# 12V_UPS1.net
KiCad netlist of a schematic drawn in EAGLE
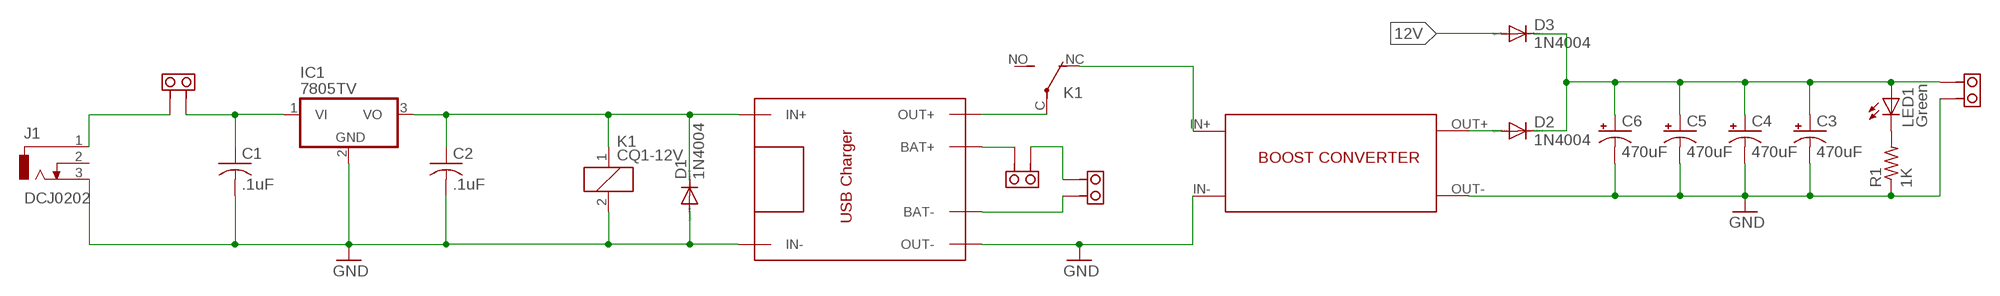
[diagram p0: schematic, sheet 1]

(export (version "E")
  (design (tool "Eeschema 10.0.6"))
  (components
    (comp (ref "C1")
      (value ".1uF")
      (footprint "eagle-import:C025-030X050")
      (libsource (lib "eagle-import") (part "C-US025-030X050"))
    )
    (comp (ref "C2")
      (value ".1uF")
      (footprint "eagle-import:C025-030X050")
      (libsource (lib "eagle-import") (part "C-US025-030X050"))
    )
    (comp (ref "C3")
      (value "470uF")
      (footprint "eagle-import:E5-8,5")
      (libsource (lib "eagle-import") (part "CPOL-USE5-8.5"))
    )
    (comp (ref "C4")
      (value "470uF")
      (footprint "eagle-import:E5-8,5")
      (libsource (lib "eagle-import") (part "CPOL-USE5-8.5"))
    )
    (comp (ref "C5")
      (value "470uF")
      (footprint "eagle-import:E5-8,5")
      (libsource (lib "eagle-import") (part "CPOL-USE5-8.5"))
    )
    (comp (ref "C6")
      (value "470uF")
      (footprint "eagle-import:E5-8,5")
      (libsource (lib "eagle-import") (part "CPOL-USE5-8.5"))
    )
    (comp (ref "D1")
      (value "1N4004")
      (footprint "eagle-import:DO41-10")
      (libsource (lib "eagle-import") (part "1N4004"))
    )
    (comp (ref "D2")
      (value "1N4004")
      (footprint "eagle-import:DO41-10")
      (libsource (lib "eagle-import") (part "1N4004"))
    )
    (comp (ref "D3")
      (value "1N4004")
      (footprint "eagle-import:DO41-10")
      (libsource (lib "eagle-import") (part "1N4004"))
    )
    (comp (ref "IC1")
      (value "7805TV")
      (footprint "eagle-import:TO220V")
      (libsource (lib "eagle-import") (part "78TV05"))
    )
    (comp (ref "J1")
      (value "DCJ0202")
      (footprint "eagle-import:DCJ0202")
      (libsource (lib "eagle-import") (part "DCJ0202"))
    )
    (comp (ref "K1")
      (value "CQ1-12V")
      (footprint "eagle-import:CQ1")
      (libsource (lib "eagle-import") (part "CQ1-12V"))
    )
    (comp (ref "LED1")
      (value "Green")
      (footprint "eagle-import:LED5MM")
      (libsource (lib "eagle-import") (part "LED5MM"))
    )
    (comp (ref "R1")
      (value "1K")
      (footprint "eagle-import:0204V")
      (libsource (lib "eagle-import") (part "R-US_0204/2V"))
    )
    (comp (ref "U$1")
      (value "TP4056_TH")
      (footprint "eagle-import:TP4056_TH")
      (libsource (lib "eagle-import") (part "TP4056_TH"))
    )
    (comp (ref "U$2")
      (value "BOOST")
      (footprint "eagle-import:BOOST")
      (libsource (lib "eagle-import") (part "BOOST"))
    )
    (comp (ref "U$3")
      (value "BERG_2")
      (footprint "eagle-import:BERG_2")
      (libsource (lib "eagle-import") (part "BERG_2"))
    )
    (comp (ref "U$4")
      (value "BERG_2")
      (footprint "eagle-import:BERG_2")
      (libsource (lib "eagle-import") (part "BERG_2"))
    )
    (comp (ref "U$5")
      (value "BERG_2")
      (footprint "eagle-import:BERG_2")
      (libsource (lib "eagle-import") (part "BERG_2"))
    )
    (comp (ref "U$6")
      (value "BERG_2")
      (footprint "eagle-import:BERG_2")
      (libsource (lib "eagle-import") (part "BERG_2"))
    )
  )
  (nets
    (net (code "1") (name "12V") (class "Default")
      (node (ref "D3") (pin "A") (pinfunction "A_A") (pintype "passive"))
      (node (ref "J1") (pin "1") (pinfunction "1_1") (pintype "passive"))
      (node (ref "U$4") (pin "F") (pinfunction "P$2_F") (pintype "bidirectional"))
    )
    (net (code "2") (name "GND") (class "Default")
      (node (ref "C1") (pin "2") (pinfunction "2_2") (pintype "passive"))
      (node (ref "C2") (pin "2") (pinfunction "2_2") (pintype "passive"))
      (node (ref "C3") (pin "-") (pinfunction "-_-") (pintype "passive"))
      (node (ref "C4") (pin "-") (pinfunction "-_-") (pintype "passive"))
      (node (ref "C5") (pin "-") (pinfunction "-_-") (pintype "passive"))
      (node (ref "C6") (pin "-") (pinfunction "-_-") (pintype "passive"))
      (node (ref "D1") (pin "A") (pinfunction "A_A") (pintype "passive"))
      (node (ref "IC1") (pin "2") (pinfunction "GND_2") (pintype "passive"))
      (node (ref "J1") (pin "3") (pinfunction "3_3") (pintype "passive"))
      (node (ref "K1") (pin "2") (pinfunction "2_2") (pintype "passive"))
      (node (ref "R1") (pin "1") (pinfunction "1_1") (pintype "passive"))
      (node (ref "U$1") (pin "IN-") (pinfunction "IN-_IN-") (pintype "bidirectional"))
      (node (ref "U$1") (pin "OUT-") (pinfunction "OUT-_OUT-") (pintype "bidirectional"))
      (node (ref "U$2") (pin "IN-") (pinfunction "IN-_IN-") (pintype "bidirectional"))
      (node (ref "U$2") (pin "OUT-") (pinfunction "OUT-_OUT-") (pintype "bidirectional"))
      (node (ref "U$3") (pin "E") (pinfunction "P$1_E") (pintype "bidirectional"))
    )
    (net (code "3") (name "Net-(D2-PadA)") (class "Default")
      (node (ref "D2") (pin "A") (pinfunction "A_A") (pintype "passive"))
      (node (ref "U$2") (pin "OUT+") (pinfunction "OUT+_OUT+") (pintype "bidirectional"))
    )
    (net (code "4") (name "Net-(IC1-VI)") (class "Default")
      (node (ref "C1") (pin "1") (pinfunction "1_1") (pintype "passive"))
      (node (ref "IC1") (pin "1") (pinfunction "VI_1") (pintype "input"))
      (node (ref "U$4") (pin "E") (pinfunction "P$1_E") (pintype "bidirectional"))
    )
    (net (code "5") (name "Net-(IC1-VO)") (class "Default")
      (node (ref "C2") (pin "1") (pinfunction "1_1") (pintype "passive"))
      (node (ref "D1") (pin "C") (pinfunction "C_C") (pintype "passive"))
      (node (ref "IC1") (pin "3") (pinfunction "VO_3") (pintype "passive"))
      (node (ref "K1") (pin "1") (pinfunction "1_1") (pintype "passive"))
      (node (ref "U$1") (pin "IN+") (pinfunction "IN+_IN+") (pintype "bidirectional"))
    )
    (net (code "6") (name "Net-(K1B-O)") (class "Default")
      (node (ref "K1") (pin "NC") (pinfunction "O_NC") (pintype "passive"))
      (node (ref "U$2") (pin "IN+") (pinfunction "IN+_IN+") (pintype "bidirectional"))
    )
    (net (code "7") (name "Net-(K1B-P)") (class "Default")
      (node (ref "K1") (pin "C") (pinfunction "P_C") (pintype "passive"))
      (node (ref "U$1") (pin "OUT+") (pinfunction "OUT+_OUT+") (pintype "bidirectional"))
    )
    (net (code "8") (name "Net-(LED1-C)") (class "Default")
      (node (ref "LED1") (pin "K") (pinfunction "C_K") (pintype "passive"))
      (node (ref "R1") (pin "2") (pinfunction "2_2") (pintype "passive"))
    )
    (net (code "9") (name "Net-(U$3-P$2)") (class "Default")
      (node (ref "C3") (pin "+") (pinfunction "+_+") (pintype "passive"))
      (node (ref "C4") (pin "+") (pinfunction "+_+") (pintype "passive"))
      (node (ref "C5") (pin "+") (pinfunction "+_+") (pintype "passive"))
      (node (ref "C6") (pin "+") (pinfunction "+_+") (pintype "passive"))
      (node (ref "D2") (pin "C") (pinfunction "C_C") (pintype "passive"))
      (node (ref "D3") (pin "C") (pinfunction "C_C") (pintype "passive"))
      (node (ref "LED1") (pin "A") (pinfunction "A_A") (pintype "passive"))
      (node (ref "U$3") (pin "F") (pinfunction "P$2_F") (pintype "bidirectional"))
    )
    (net (code "10") (name "Net-(U$5-P$1)") (class "Default")
      (node (ref "U$1") (pin "BAT-") (pinfunction "BAT-_BAT-") (pintype "bidirectional"))
      (node (ref "U$5") (pin "E") (pinfunction "P$1_E") (pintype "bidirectional"))
    )
    (net (code "11") (name "Net-(U$5-P$2)") (class "Default")
      (node (ref "U$5") (pin "F") (pinfunction "P$2_F") (pintype "bidirectional"))
      (node (ref "U$6") (pin "F") (pinfunction "P$2_F") (pintype "bidirectional"))
    )
    (net (code "12") (name "Net-(U$6-P$1)") (class "Default")
      (node (ref "U$1") (pin "BAT+") (pinfunction "BAT+_BAT+") (pintype "bidirectional"))
      (node (ref "U$6") (pin "E") (pinfunction "P$1_E") (pintype "bidirectional"))
    )
    (net (code "13") (name "unconnected-(J1-Pad2)") (class "Default")
      (node (ref "J1") (pin "2") (pinfunction "2_2") (pintype "passive"))
    )
    (net (code "14") (name "unconnected-(K1B-S-PadNO)") (class "Default")
      (node (ref "K1") (pin "NO") (pinfunction "S_NO") (pintype "passive"))
    )
  )
)
